# NanoBoard.net
KiCad netlist of a schematic drawn in EAGLE
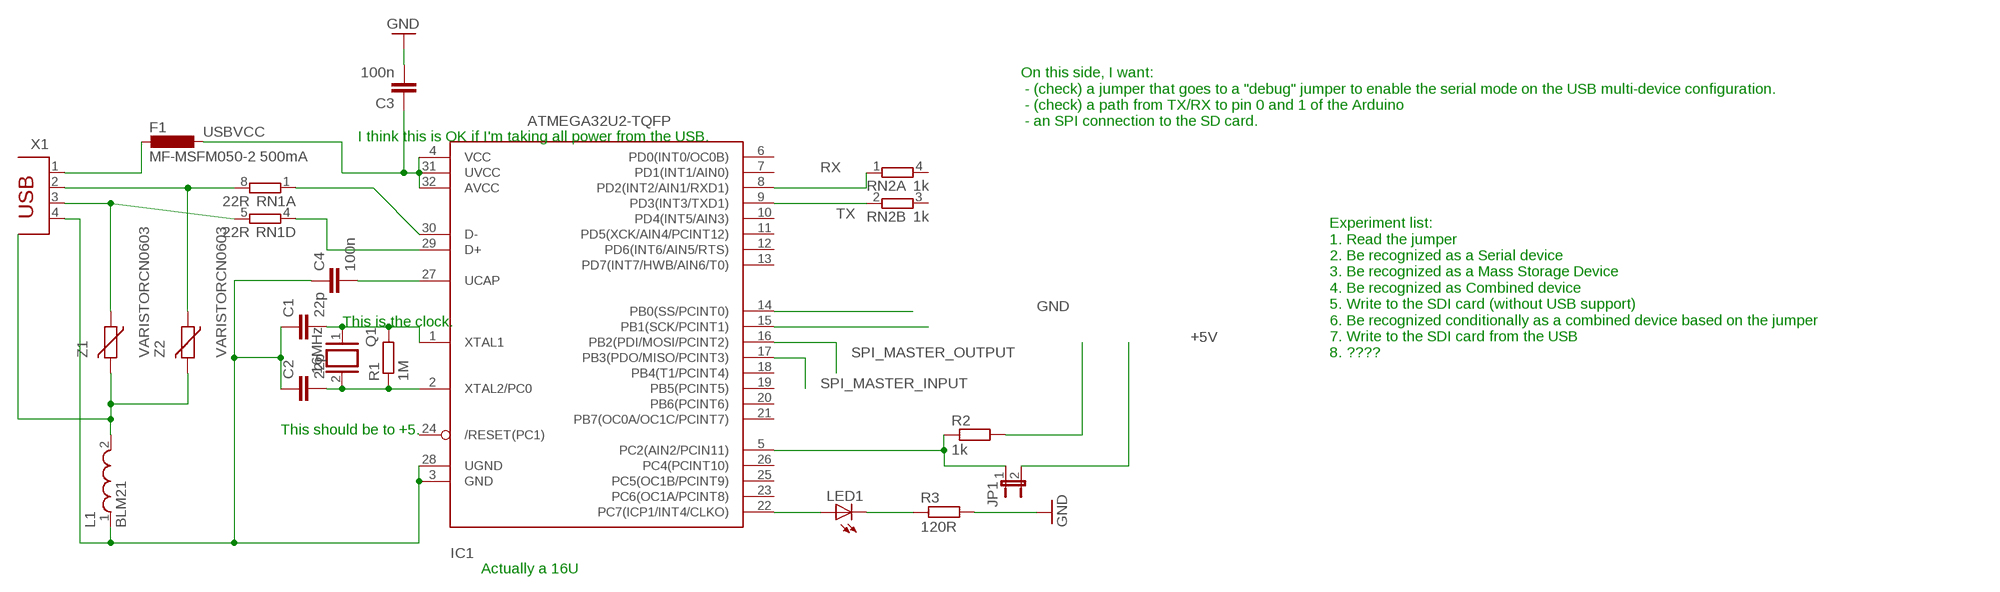
[diagram p0: schematic, sheet 1]

(export (version "E")
  (design (tool "Eeschema 10.0.6"))
  (components
    (comp (ref "C1")
      (value "22p")
      (footprint "eagle-import:C2.5-2")
      (libsource (lib "eagle-import") (part "C2.5/2"))
    )
    (comp (ref "C2")
      (value "22p")
      (footprint "eagle-import:C2.5-2")
      (libsource (lib "eagle-import") (part "C2.5/2"))
    )
    (comp (ref "C3")
      (value "100n")
      (footprint "eagle-import:C2.5-2")
      (libsource (lib "eagle-import") (part "C2.5/2"))
    )
    (comp (ref "C4")
      (value "100n")
      (footprint "eagle-import:C2.5-3")
      (libsource (lib "eagle-import") (part "C2,5-3"))
    )
    (comp (ref "F1")
      (value "MF-MSFM050-2 500mA")
      (footprint "eagle-import:L1812")
      (libsource (lib "eagle-import") (part "L-EUL1812"))
    )
    (comp (ref "IC1")
      (value "ATMEGA32U2-TQFP")
      (footprint "eagle-import:TQFP32-08")
      (libsource (lib "eagle-import") (part "ATMEGA32U2-TQFP"))
    )
    (comp (ref "JP1")
      (value "JP1E")
      (footprint "eagle-import:JP1")
      (libsource (lib "eagle-import") (part "JP1E"))
    )
    (comp (ref "L1")
      (value "BLM21")
      (footprint "eagle-import:WE-CBF_0805(W=3.0)")
      (libsource (lib "eagle-import") (part "WE-CBF_0805(WB/HS)"))
    )
    (comp (ref "LED1")
      (value "LED")
      (footprint "eagle-import:SMARTLED-TTW")
      (libsource (lib "eagle-import") (part "LED"))
    )
    (comp (ref "Q1")
      (value "16MHz")
      (footprint "eagle-import:QS")
      (libsource (lib "eagle-import") (part "XTAL/S"))
    )
    (comp (ref "R1")
      (value "1M")
      (footprint "eagle-import:R0603")
      (libsource (lib "eagle-import") (part "R-EU_R0603"))
    )
    (comp (ref "R2")
      (value "1k")
      (footprint "eagle-import:0204V")
      (libsource (lib "eagle-import") (part "R-EU_0204/2V"))
    )
    (comp (ref "R3")
      (value "120R")
      (footprint "eagle-import:0204V")
      (libsource (lib "eagle-import") (part "R-EU_0204/2V"))
    )
    (comp (ref "RN1")
      (value "22R")
      (footprint "eagle-import:CAY16")
      (libsource (lib "eagle-import") (part "4R-NCAY16"))
    )
    (comp (ref "RN2")
      (value "1k")
      (footprint "eagle-import:EXB14V")
      (libsource (lib "eagle-import") (part "2R-NEXB14V"))
    )
    (comp (ref "X1")
      (value "PN61729")
      (footprint "eagle-import:PN61729")
      (libsource (lib "eagle-import") (part "PN61729"))
    )
    (comp (ref "Z1")
      (value "VARISTORCN0603")
      (footprint "eagle-import:CT_CN0603")
      (libsource (lib "eagle-import") (part "VARISTORCN0603"))
    )
    (comp (ref "Z2")
      (value "VARISTORCN0603")
      (footprint "eagle-import:CT_CN0603")
      (libsource (lib "eagle-import") (part "VARISTORCN0603"))
    )
  )
  (nets
    (net (code "1") (name "/+5V") (class "Default")
      (node (ref "JP1") (pin "2") (pinfunction "2_2") (pintype "passive"))
    )
    (net (code "2") (name "/RX") (class "Default")
      (node (ref "IC1") (pin "8") (pinfunction "PD2(INT2/AIN1/RXD1)_8") (pintype "bidirectional"))
      (node (ref "RN2") (pin "1") (pinfunction "1_1") (pintype "passive"))
    )
    (net (code "3") (name "/SPI_MASTER_INPUT") (class "Default")
      (node (ref "IC1") (pin "17") (pinfunction "PB3(PDO/MISO/PCINT3)_17") (pintype "bidirectional"))
    )
    (net (code "4") (name "/SPI_MASTER_OUTPUT") (class "Default")
      (node (ref "IC1") (pin "16") (pinfunction "PB2(PDI/MOSI/PCINT2)_16") (pintype "bidirectional"))
    )
    (net (code "5") (name "/TX") (class "Default")
      (node (ref "IC1") (pin "9") (pinfunction "PD3(INT3/TXD1)_9") (pintype "bidirectional"))
      (node (ref "RN2") (pin "2") (pinfunction "1_2") (pintype "passive"))
    )
    (net (code "6") (name "/USBVCC") (class "Default")
      (node (ref "C3") (pin "1") (pinfunction "1_1") (pintype "passive"))
      (node (ref "F1") (pin "1") (pinfunction "1_1") (pintype "passive"))
      (node (ref "IC1") (pin "31") (pinfunction "UVCC_31") (pintype "bidirectional"))
      (node (ref "IC1") (pin "32") (pinfunction "AVCC_32") (pintype "bidirectional"))
      (node (ref "IC1") (pin "4") (pinfunction "VCC_4") (pintype "bidirectional"))
    )
    (net (code "7") (name "GND") (class "Default")
      (node (ref "C3") (pin "2") (pinfunction "2_2") (pintype "passive"))
      (node (ref "R2") (pin "2") (pinfunction "2_2") (pintype "passive"))
      (node (ref "R3") (pin "2") (pinfunction "2_2") (pintype "passive"))
    )
    (net (code "8") (name "Net-(F1-Pad2)") (class "Default")
      (node (ref "F1") (pin "2") (pinfunction "2_2") (pintype "passive"))
      (node (ref "X1") (pin "1") (pinfunction "1_1") (pintype "passive"))
    )
    (net (code "9") (name "Net-(IC1-D+)") (class "Default")
      (node (ref "IC1") (pin "29") (pinfunction "D+_29") (pintype "bidirectional"))
      (node (ref "RN1") (pin "4") (pinfunction "1_4") (pintype "passive"))
    )
    (net (code "10") (name "Net-(IC1-D-)") (class "Default")
      (node (ref "IC1") (pin "30") (pinfunction "D-_30") (pintype "bidirectional"))
      (node (ref "RN1") (pin "1") (pinfunction "1_1") (pintype "passive"))
    )
    (net (code "11") (name "Net-(IC1-GND)") (class "Default")
      (node (ref "C1") (pin "1") (pinfunction "1_1") (pintype "passive"))
      (node (ref "C2") (pin "1") (pinfunction "1_1") (pintype "passive"))
      (node (ref "C4") (pin "1") (pinfunction "1_1") (pintype "passive"))
      (node (ref "IC1") (pin "28") (pinfunction "UGND_28") (pintype "bidirectional"))
      (node (ref "IC1") (pin "3") (pinfunction "GND_3") (pintype "bidirectional"))
      (node (ref "L1") (pin "1") (pinfunction "1_1") (pintype "passive"))
      (node (ref "X1") (pin "4") (pinfunction "4_4") (pintype "passive"))
    )
    (net (code "12") (name "Net-(IC1-PC2(AIN2{slash}PCIN11))") (class "Default")
      (node (ref "IC1") (pin "5") (pinfunction "PC2(AIN2/PCIN11)_5") (pintype "bidirectional"))
      (node (ref "JP1") (pin "1") (pinfunction "1_1") (pintype "passive"))
      (node (ref "R2") (pin "1") (pinfunction "1_1") (pintype "passive"))
    )
    (net (code "13") (name "Net-(IC1-PC7(ICP1{slash}INT4{slash}CLKO))") (class "Default")
      (node (ref "IC1") (pin "22") (pinfunction "PC7(ICP1/INT4/CLKO)_22") (pintype "bidirectional"))
      (node (ref "LED1") (pin "A@1") (pinfunction "A_A@1") (pintype "passive"))
    )
    (net (code "14") (name "Net-(IC1-UCAP)") (class "Default")
      (node (ref "C4") (pin "2") (pinfunction "2_2") (pintype "passive"))
      (node (ref "IC1") (pin "27") (pinfunction "UCAP_27") (pintype "bidirectional"))
    )
    (net (code "15") (name "Net-(IC1-XTAL1)") (class "Default")
      (node (ref "C1") (pin "2") (pinfunction "2_2") (pintype "passive"))
      (node (ref "IC1") (pin "1") (pinfunction "XTAL1_1") (pintype "bidirectional"))
      (node (ref "Q1") (pin "1") (pinfunction "1_1") (pintype "passive"))
      (node (ref "R1") (pin "2") (pinfunction "2_2") (pintype "passive"))
    )
    (net (code "16") (name "Net-(IC1-XTAL2{slash}PC0)") (class "Default")
      (node (ref "C2") (pin "2") (pinfunction "2_2") (pintype "passive"))
      (node (ref "IC1") (pin "2") (pinfunction "XTAL2/PC0_2") (pintype "bidirectional"))
      (node (ref "Q1") (pin "2") (pinfunction "2_2") (pintype "passive"))
      (node (ref "R1") (pin "1") (pinfunction "1_1") (pintype "passive"))
    )
    (net (code "17") (name "Net-(L1-Pad2)") (class "Default")
      (node (ref "L1") (pin "2") (pinfunction "2_2") (pintype "passive"))
      (node (ref "Z1") (pin "2") (pinfunction "2_2") (pintype "passive"))
      (node (ref "Z2") (pin "2") (pinfunction "2_2") (pintype "passive"))
    )
    (net (code "18") (name "Net-(LED1-C)") (class "Default")
      (node (ref "LED1") (pin "C@1") (pinfunction "C_C@1") (pintype "passive"))
      (node (ref "R3") (pin "1") (pinfunction "1_1") (pintype "passive"))
    )
    (net (code "19") (name "Net-(RN1A-2)") (class "Default")
      (node (ref "RN1") (pin "8") (pinfunction "2_8") (pintype "passive"))
      (node (ref "X1") (pin "2") (pinfunction "2_2") (pintype "passive"))
      (node (ref "Z2") (pin "1") (pinfunction "1_1") (pintype "passive"))
    )
    (net (code "20") (name "Net-(RN1D-2)") (class "Default")
      (node (ref "RN1") (pin "5") (pinfunction "2_5") (pintype "passive"))
      (node (ref "X1") (pin "3") (pinfunction "3_3") (pintype "passive"))
      (node (ref "Z1") (pin "1") (pinfunction "1_1") (pintype "passive"))
    )
    (net (code "21") (name "unconnected-(IC1-PB0(SS{slash}PCINT0)-Pad14)") (class "Default")
      (node (ref "IC1") (pin "14") (pinfunction "PB0(SS/PCINT0)_14") (pintype "bidirectional"))
    )
    (net (code "22") (name "unconnected-(IC1-PB1(SCK{slash}PCINT1)-Pad15)") (class "Default")
      (node (ref "IC1") (pin "15") (pinfunction "PB1(SCK/PCINT1)_15") (pintype "bidirectional"))
    )
    (net (code "23") (name "unconnected-(IC1-PB4(T1{slash}PCINT4)-Pad18)") (class "Default")
      (node (ref "IC1") (pin "18") (pinfunction "PB4(T1/PCINT4)_18") (pintype "bidirectional"))
    )
    (net (code "24") (name "unconnected-(IC1-PB5(PCINT5)-Pad19)") (class "Default")
      (node (ref "IC1") (pin "19") (pinfunction "PB5(PCINT5)_19") (pintype "bidirectional"))
    )
    (net (code "25") (name "unconnected-(IC1-PB6(PCINT6)-Pad20)") (class "Default")
      (node (ref "IC1") (pin "20") (pinfunction "PB6(PCINT6)_20") (pintype "bidirectional"))
    )
    (net (code "26") (name "unconnected-(IC1-PB7(OC0A{slash}OC1C{slash}PCINT7)-Pad21)") (class "Default")
      (node (ref "IC1") (pin "21") (pinfunction "PB7(OC0A/OC1C/PCINT7)_21") (pintype "bidirectional"))
    )
    (net (code "27") (name "unconnected-(IC1-PC4(PCINT10)-Pad26)") (class "Default")
      (node (ref "IC1") (pin "26") (pinfunction "PC4(PCINT10)_26") (pintype "bidirectional"))
    )
    (net (code "28") (name "unconnected-(IC1-PC5(OC1B{slash}PCINT9)-Pad25)") (class "Default")
      (node (ref "IC1") (pin "25") (pinfunction "PC5(OC1B/PCINT9)_25") (pintype "bidirectional"))
    )
    (net (code "29") (name "unconnected-(IC1-PC6(OC1A{slash}PCINT8)-Pad23)") (class "Default")
      (node (ref "IC1") (pin "23") (pinfunction "PC6(OC1A/PCINT8)_23") (pintype "bidirectional"))
    )
    (net (code "30") (name "unconnected-(IC1-PD0(INT0{slash}OC0B)-Pad6)") (class "Default")
      (node (ref "IC1") (pin "6") (pinfunction "PD0(INT0/OC0B)_6") (pintype "bidirectional"))
    )
    (net (code "31") (name "unconnected-(IC1-PD1(INT1{slash}AIN0)-Pad7)") (class "Default")
      (node (ref "IC1") (pin "7") (pinfunction "PD1(INT1/AIN0)_7") (pintype "bidirectional"))
    )
    (net (code "32") (name "unconnected-(IC1-PD4(INT5{slash}AIN3)-Pad10)") (class "Default")
      (node (ref "IC1") (pin "10") (pinfunction "PD4(INT5/AIN3)_10") (pintype "bidirectional"))
    )
    (net (code "33") (name "unconnected-(IC1-PD5(XCK{slash}AIN4{slash}PCINT12)-Pad11)") (class "Default")
      (node (ref "IC1") (pin "11") (pinfunction "PD5(XCK/AIN4/PCINT12)_11") (pintype "bidirectional"))
    )
    (net (code "34") (name "unconnected-(IC1-PD6(INT6{slash}AIN5{slash}RTS)-Pad12)") (class "Default")
      (node (ref "IC1") (pin "12") (pinfunction "PD6(INT6/AIN5/RTS)_12") (pintype "bidirectional"))
    )
    (net (code "35") (name "unconnected-(IC1-PD7(INT7{slash}HWB{slash}AIN6{slash}T0)-Pad13)") (class "Default")
      (node (ref "IC1") (pin "13") (pinfunction "PD7(INT7/HWB/AIN6/T0)_13") (pintype "bidirectional"))
    )
    (net (code "36") (name "unconnected-(IC1-{slash}RESET(PC1)-Pad24)") (class "Default")
      (node (ref "IC1") (pin "24") (pinfunction "/RESET(PC1)_24") (pintype "bidirectional"))
    )
    (net (code "37") (name "unconnected-(RN2A-2-Pad4)") (class "Default")
      (node (ref "RN2") (pin "4") (pinfunction "2_4") (pintype "passive"))
    )
    (net (code "38") (name "unconnected-(RN2B-2-Pad3)") (class "Default")
      (node (ref "RN2") (pin "3") (pinfunction "2_3") (pintype "passive"))
    )
  )
)
